# Adafruit-FONA-800-GSM-Breakout.net
KiCad netlist of a schematic drawn in EAGLE
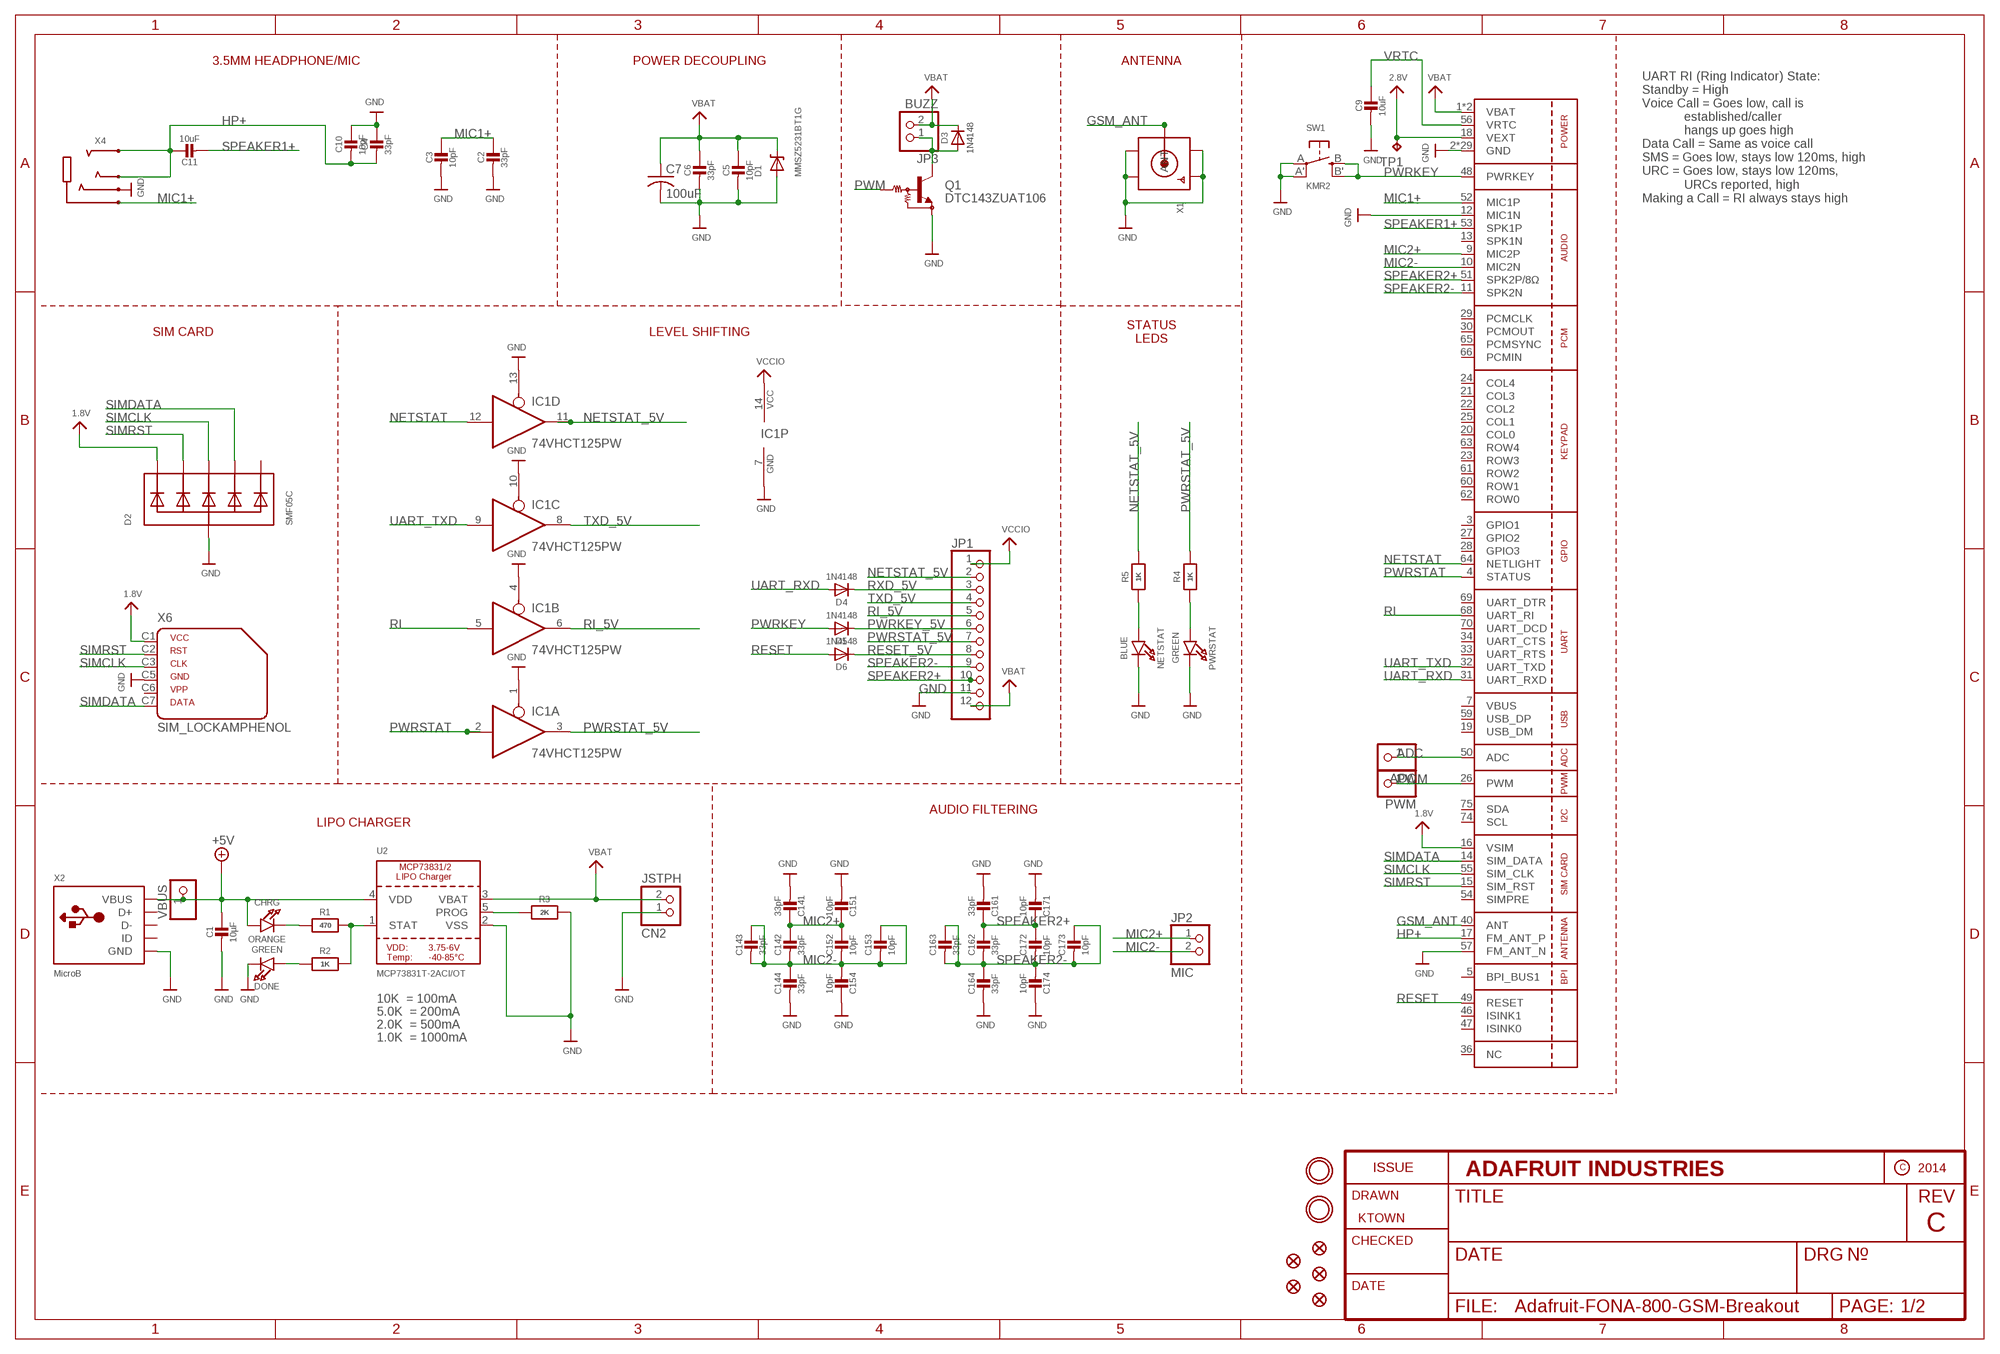
[diagram p0: schematic, sheet 1]
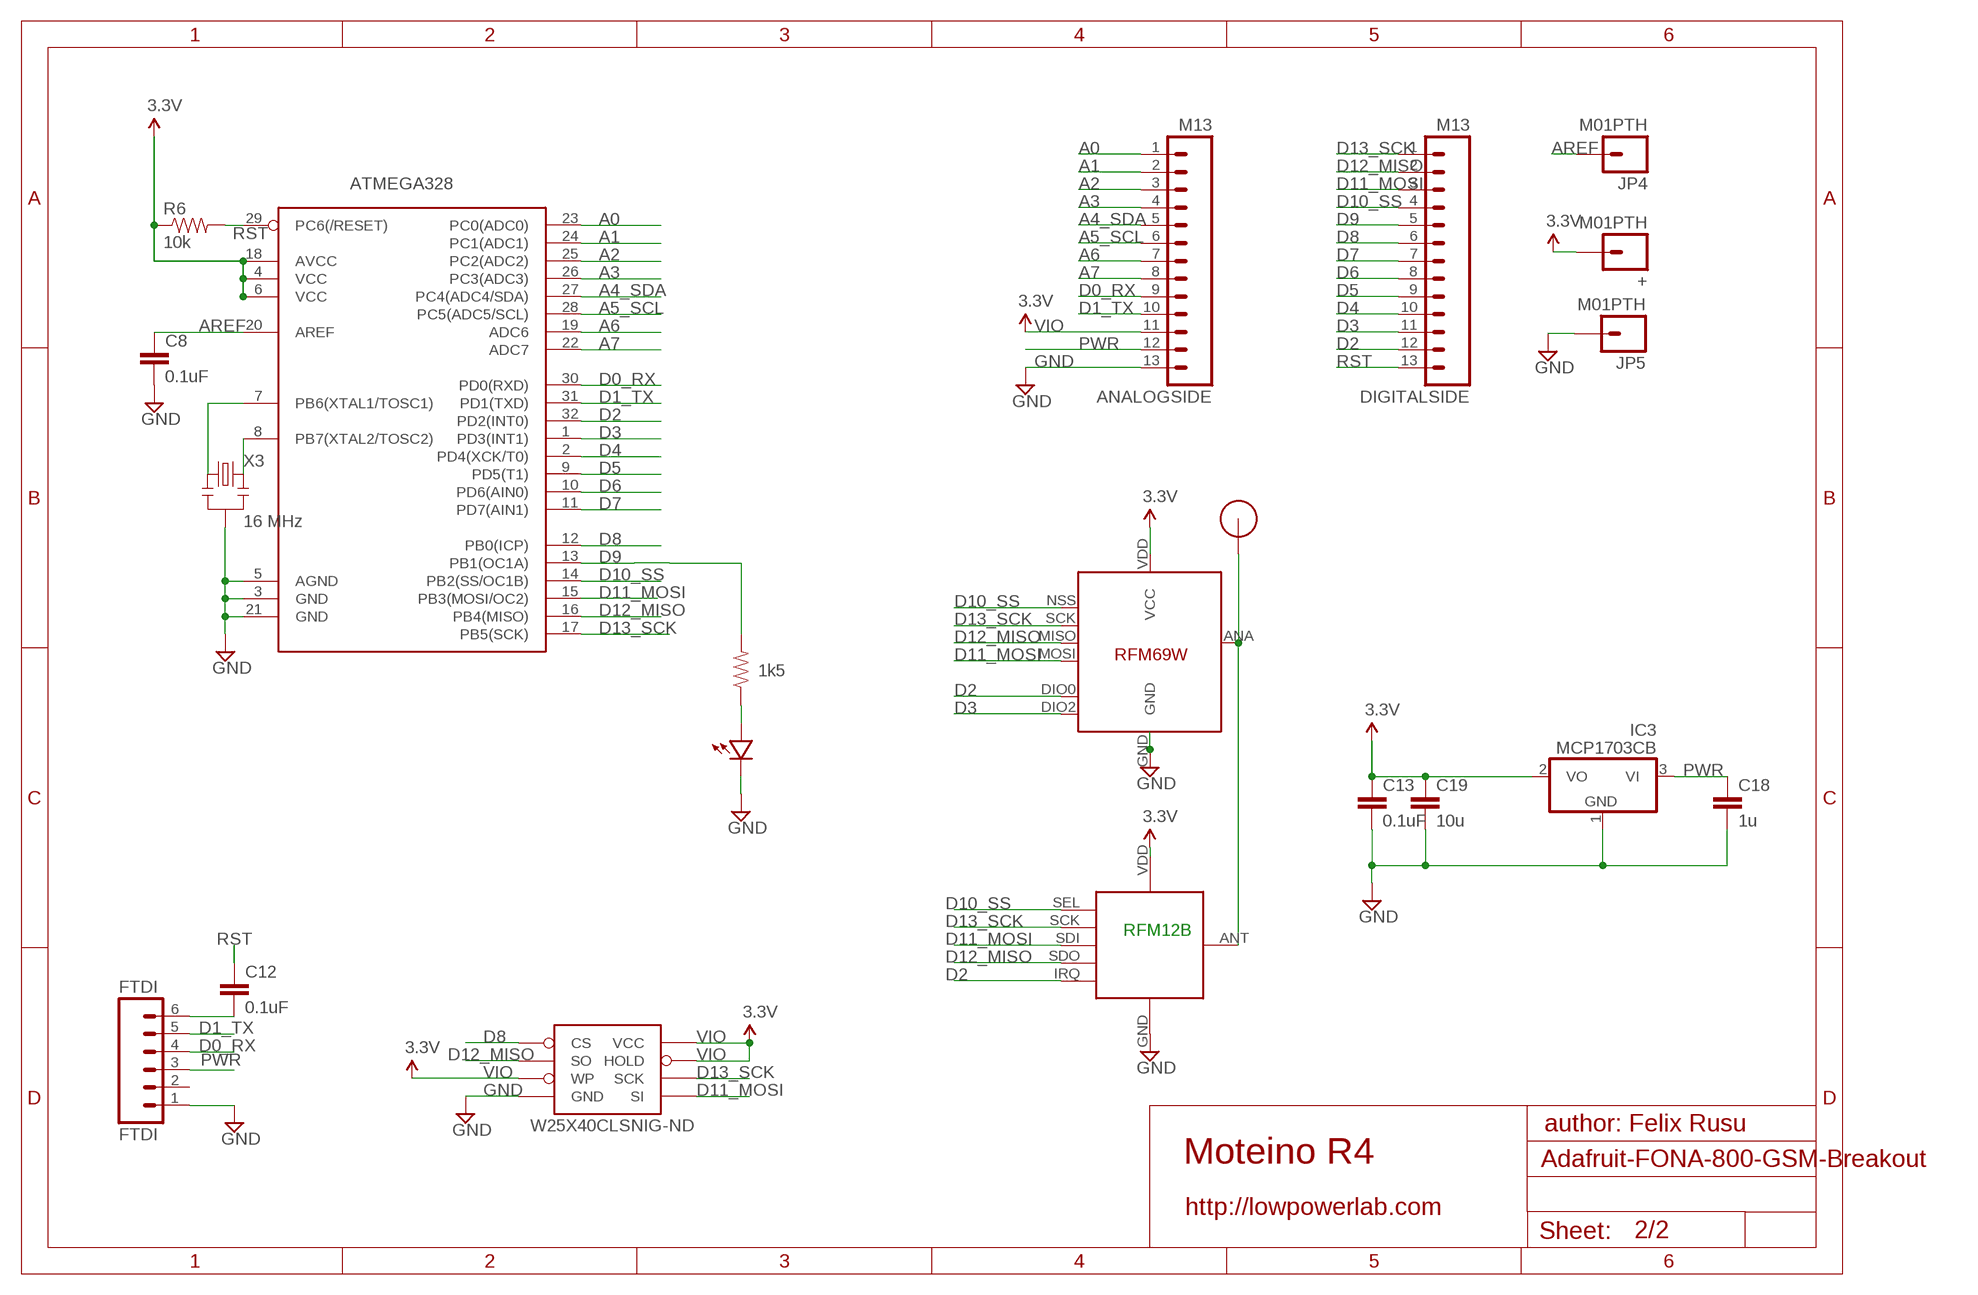
[diagram p1: schematic, sheet 2]

(export (version "E")
  (design (tool "Eeschema 10.0.6"))
  (components
    (comp (ref "ADC")
      (value "PINHD-1X1CB")
      (footprint "eagle-import:1X01-CLEANBIG")
      (libsource (lib "eagle-import") (part "PINHD-1X1CB"))
    )
    (comp (ref "C1")
      (value "10µF")
      (footprint "eagle-import:0805-NO")
      (libsource (lib "eagle-import") (part "CAP_CERAMIC0805-NOOUTLINE"))
    )
    (comp (ref "C2")
      (value "33pF")
      (footprint "eagle-import:0805-NO")
      (libsource (lib "eagle-import") (part "CAP_CERAMIC0805-NOOUTLINE"))
    )
    (comp (ref "C3")
      (value "10pF")
      (footprint "eagle-import:0805-NO")
      (libsource (lib "eagle-import") (part "CAP_CERAMIC0805-NOOUTLINE"))
    )
    (comp (ref "C4")
      (value "33pF")
      (footprint "eagle-import:0805-NO")
      (libsource (lib "eagle-import") (part "CAP_CERAMIC0805-NOOUTLINE"))
    )
    (comp (ref "C5")
      (value "10pF")
      (footprint "eagle-import:0805-NO")
      (libsource (lib "eagle-import") (part "CAP_CERAMIC0805-NOOUTLINE"))
    )
    (comp (ref "C6")
      (value "33pF")
      (footprint "eagle-import:0805-NO")
      (libsource (lib "eagle-import") (part "CAP_CERAMIC0805-NOOUTLINE"))
    )
    (comp (ref "C7")
      (value "100uF")
      (footprint "eagle-import:C1210")
      (libsource (lib "eagle-import") (part "C-USC1210"))
    )
    (comp (ref "C9")
      (value "10uF")
      (footprint "eagle-import:0805-NO")
      (libsource (lib "eagle-import") (part "CAP_CERAMIC0805-NOOUTLINE"))
    )
    (comp (ref "C10")
      (value "10pF")
      (footprint "eagle-import:0805-NO")
      (libsource (lib "eagle-import") (part "CAP_CERAMIC0805-NOOUTLINE"))
    )
    (comp (ref "C11")
      (value "10uF")
      (footprint "eagle-import:0805-NO")
      (libsource (lib "eagle-import") (part "CAP_CERAMIC0805-NOOUTLINE"))
    )
    (comp (ref "C14")
      (value "33pF")
      (footprint "eagle-import:RESPACK_4X0603")
      (libsource (lib "eagle-import") (part "CAP_4PACK1206"))
    )
    (comp (ref "C15")
      (value "10pF")
      (footprint "eagle-import:RESPACK_4X0603")
      (libsource (lib "eagle-import") (part "CAP_4PACK1206"))
    )
    (comp (ref "C16")
      (value "33pF")
      (footprint "eagle-import:RESPACK_4X0603")
      (libsource (lib "eagle-import") (part "CAP_4PACK1206"))
    )
    (comp (ref "C17")
      (value "10pF")
      (footprint "eagle-import:RESPACK_4X0603")
      (libsource (lib "eagle-import") (part "CAP_4PACK1206"))
    )
    (comp (ref "CHRG")
      (value "ORANGE")
      (footprint "eagle-import:CHIPLED_0805_NOOUTLINE")
      (libsource (lib "eagle-import") (part "LED0805_NOOUTLINE"))
    )
    (comp (ref "CN2")
      (value "JSTPH")
      (footprint "eagle-import:JSTPH2")
      (libsource (lib "eagle-import") (part "JST_2PIN"))
    )
    (comp (ref "D1")
      (value "MMSZ5231BT1G")
      (footprint "eagle-import:SOD-123")
      (libsource (lib "eagle-import") (part "DIODE-ZENERSOD123"))
    )
    (comp (ref "D2")
      (value "SMF05C")
      (footprint "eagle-import:SOT363")
      (libsource (lib "eagle-import") (part "TVSARRAY_5LANE"))
    )
    (comp (ref "D3")
      (value "1N4148")
      (footprint "eagle-import:SOD-323")
      (libsource (lib "eagle-import") (part "DIODESOD-323"))
    )
    (comp (ref "D4")
      (value "1N4148")
      (footprint "eagle-import:SOD-323")
      (libsource (lib "eagle-import") (part "DIODESOD-323"))
    )
    (comp (ref "D5")
      (value "1N4148")
      (footprint "eagle-import:SOD-323")
      (libsource (lib "eagle-import") (part "DIODESOD-323"))
    )
    (comp (ref "D6")
      (value "1N4148")
      (footprint "eagle-import:SOD-323")
      (libsource (lib "eagle-import") (part "DIODESOD-323"))
    )
    (comp (ref "DONE")
      (value "GREEN")
      (footprint "eagle-import:CHIPLED_0805_NOOUTLINE")
      (libsource (lib "eagle-import") (part "LED0805_NOOUTLINE"))
    )
    (comp (ref "FID1")
      (value "FIDUCIAL\"\"")
      (footprint "eagle-import:FIDUCIAL_1MM")
      (libsource (lib "eagle-import") (part "FIDUCIAL{dblquote}{dblquote}"))
    )
    (comp (ref "FID2")
      (value "FIDUCIAL\"\"")
      (footprint "eagle-import:FIDUCIAL_1MM")
      (libsource (lib "eagle-import") (part "FIDUCIAL{dblquote}{dblquote}"))
    )
    (comp (ref "FID3")
      (value "FIDUCIAL\"\"")
      (footprint "eagle-import:FIDUCIAL_1MM")
      (libsource (lib "eagle-import") (part "FIDUCIAL{dblquote}{dblquote}"))
    )
    (comp (ref "FID4")
      (value "FIDUCIAL\"\"")
      (footprint "eagle-import:FIDUCIAL_1MM")
      (libsource (lib "eagle-import") (part "FIDUCIAL{dblquote}{dblquote}"))
    )
    (comp (ref "FID5")
      (value "FIDUCIAL\"\"")
      (footprint "eagle-import:FIDUCIAL_1MM")
      (libsource (lib "eagle-import") (part "FIDUCIAL{dblquote}{dblquote}"))
    )
    (comp (ref "IC1")
      (value "74VHCT125PW")
      (footprint "eagle-import:TSSOP14")
      (libsource (lib "eagle-import") (part "74125PWABT"))
    )
    (comp (ref "JP1")
      (value "PINHD-1X12-CB")
      (footprint "eagle-import:1X12-CB")
      (libsource (lib "eagle-import") (part "PINHD-1X12-CB"))
    )
    (comp (ref "JP2")
      (value "MIC")
      (footprint "eagle-import:1X02_ROUND")
      (libsource (lib "eagle-import") (part "HEADER-1X2ROUND"))
    )
    (comp (ref "JP3")
      (value "BUZZ")
      (footprint "eagle-import:1X02_ROUND")
      (libsource (lib "eagle-import") (part "HEADER-1X2ROUND"))
    )
    (comp (ref "NETSTAT")
      (value "BLUE")
      (footprint "eagle-import:CHIPLED_0805_NOOUTLINE")
      (libsource (lib "eagle-import") (part "LED0805_NOOUTLINE"))
    )
    (comp (ref "PWM")
      (value "PINHD-1X1CB")
      (footprint "eagle-import:1X01-CLEANBIG")
      (libsource (lib "eagle-import") (part "PINHD-1X1CB"))
    )
    (comp (ref "PWRSTAT")
      (value "GREEN")
      (footprint "eagle-import:CHIPLED_0805_NOOUTLINE")
      (libsource (lib "eagle-import") (part "LED0805_NOOUTLINE"))
    )
    (comp (ref "Q1")
      (value "DTC143ZUAT106")
      (footprint "eagle-import:SC59-BEC")
      (libsource (lib "eagle-import") (part "-NPN_DRIVER-SC59-BECMUN2211T1"))
    )
    (comp (ref "R1")
      (value "470")
      (footprint "eagle-import:0805-NO")
      (libsource (lib "eagle-import") (part "RESISTOR0805_NOOUTLINE"))
    )
    (comp (ref "R2")
      (value "1K")
      (footprint "eagle-import:0805-NO")
      (libsource (lib "eagle-import") (part "RESISTOR0805_NOOUTLINE"))
    )
    (comp (ref "R3")
      (value "2K")
      (footprint "eagle-import:0805-NO")
      (libsource (lib "eagle-import") (part "RESISTOR0805_NOOUTLINE"))
    )
    (comp (ref "R4")
      (value "1K")
      (footprint "eagle-import:0805-NO")
      (libsource (lib "eagle-import") (part "RESISTOR0805_NOOUTLINE"))
    )
    (comp (ref "R5")
      (value "1K")
      (footprint "eagle-import:0805-NO")
      (libsource (lib "eagle-import") (part "RESISTOR0805_NOOUTLINE"))
    )
    (comp (ref "SW1")
      (value "KMR2")
      (footprint "eagle-import:BTN_KMR2_4.6X2.8")
      (libsource (lib "eagle-import") (part "SWITCH_TACT_SMT4.6X2.8"))
    )
    (comp (ref "TP1")
      (value "TPTP11R")
      (footprint "eagle-import:TP11R")
      (libsource (lib "eagle-import") (part "TPTP11R"))
    )
    (comp (ref "U$33")
      (value "MOUNTINGHOLE2.5")
      (footprint "eagle-import:MOUNTINGHOLE_2.5_PLATED")
      (libsource (lib "eagle-import") (part "MOUNTINGHOLE2.5"))
    )
    (comp (ref "U$34")
      (value "MOUNTINGHOLE2.5")
      (footprint "eagle-import:MOUNTINGHOLE_2.5_PLATED")
      (libsource (lib "eagle-import") (part "MOUNTINGHOLE2.5"))
    )
    (comp (ref "U1")
      (value "SIM800H/L")
      (footprint "eagle-import:SIM800L")
      (libsource (lib "eagle-import") (part "GSM_SIM800L"))
    )
    (comp (ref "U2")
      (value "MCP73831T-2ACI/OT")
      (footprint "eagle-import:SOT23-5")
      (libsource (lib "eagle-import") (part "MCP73831/2"))
    )
    (comp (ref "VBUS")
      (value "PINHD-1X1CB")
      (footprint "eagle-import:1X01-CLEANBIG")
      (libsource (lib "eagle-import") (part "PINHD-1X1CB"))
    )
    (comp (ref "X1")
      (value "SMACONNECTOR_EDGE_UFL")
      (footprint "eagle-import:SMA_EDGELAUNCH_UFL")
      (libsource (lib "eagle-import") (part "SMACONNECTOR_EDGE_UFL"))
    )
    (comp (ref "X2")
      (value "MicroB")
      (footprint "eagle-import:4UCONN_20329")
      (libsource (lib "eagle-import") (part "USBMICRO_20329"))
    )
    (comp (ref "X4")
      (value "AUDIO_3.5MMJACK_4POL")
      (footprint "eagle-import:4UCONN_18510")
      (libsource (lib "eagle-import") (part "AUDIO_3.5MMJACK_4POL"))
    )
    (comp (ref "X6")
      (value "SIM_LOCKAMPHENOL")
      (footprint "eagle-import:C707_10M006_512_2")
      (libsource (lib "eagle-import") (part "SIM_LOCKAMPHENOL"))
    )
    (comp (ref "+")
      (value "M01PTH")
      (footprint "eagle-import:1X01")
      (libsource (lib "eagle-import") (part "M01PTH"))
    )
    (comp (ref "ANALOGSIDE")
      (value "M13")
      (footprint "eagle-import:1X13")
      (libsource (lib "eagle-import") (part "M13"))
    )
    (comp (ref "ATMEGA328")
      (value "ATMega-328")
      (footprint "eagle-import:TQFP32-08")
      (libsource (lib "eagle-import") (part "ATMEGA168/328TQFP32"))
    )
    (comp (ref "C8")
      (value "0.1uF")
      (footprint "eagle-import:0603-CAP")
      (libsource (lib "eagle-import") (part "CAP0603-CAP"))
    )
    (comp (ref "C12")
      (value "0.1uF")
      (footprint "eagle-import:0603-CAP")
      (libsource (lib "eagle-import") (part "CAP0603-CAP"))
    )
    (comp (ref "C13")
      (value "0.1uF")
      (footprint "eagle-import:0603-CAP")
      (libsource (lib "eagle-import") (part "CAP0603-CAP"))
    )
    (comp (ref "C18")
      (value "1u")
      (footprint "eagle-import:0603-CAP")
      (libsource (lib "eagle-import") (part "CAP0603-CAP"))
    )
    (comp (ref "C19")
      (value "10u")
      (footprint "eagle-import:0805-CAP")
      (libsource (lib "eagle-import") (part "CAP0805-CAP"))
    )
    (comp (ref "DIGITALSIDE")
      (value "M13")
      (footprint "eagle-import:1X13")
      (libsource (lib "eagle-import") (part "M13"))
    )
    (comp (ref "FTDI")
      (value "FTDI")
      (footprint "eagle-import:1X06")
      (libsource (lib "eagle-import") (part "M06SIP"))
    )
    (comp (ref "IC3")
      (value "MCP1703CB")
      (footprint "eagle-import:SOT23")
      (libsource (lib "eagle-import") (part "MCP1703CB"))
    )
    (comp (ref "JP4")
      (value "M01PTH")
      (footprint "eagle-import:1X01")
      (libsource (lib "eagle-import") (part "M01PTH"))
    )
    (comp (ref "JP5")
      (value "M01PTH")
      (footprint "eagle-import:1X01")
      (libsource (lib "eagle-import") (part "M01PTH"))
    )
    (comp (ref "R6")
      (value "10k")
      (footprint "eagle-import:0603-RES")
      (libsource (lib "eagle-import") (part "RESISTOR0603-RES"))
    )
    (comp (ref "R7")
      (value "1k5")
      (footprint "eagle-import:0603-RES")
      (libsource (lib "eagle-import") (part "RESISTOR0603-RES"))
    )
    (comp (ref "RFM12B")
      (value "RFM12B_MINPADS")
      (footprint "eagle-import:RFM12B-MINPADS")
      (libsource (lib "eagle-import") (part "RFM12B_MINPADS"))
    )
    (comp (ref "U$38")
      (value "LED0603")
      (footprint "eagle-import:0603-LED")
      (libsource (lib "eagle-import") (part "LED0603"))
    )
    (comp (ref "U$39")
      (value "RFM12B_ANTENNA")
      (footprint "eagle-import:RFM12B-ANTENNA")
      (libsource (lib "eagle-import") (part "RFM12B_ANTENNA"))
    )
    (comp (ref "U$42")
      (value "RFM69")
      (footprint "eagle-import:RFM69W-MINPADS")
      (libsource (lib "eagle-import") (part "RFM69"))
    )
    (comp (ref "W25X40CLSNIG-ND")
      (value "AT25F512BWIDE_5.3MM")
      (footprint "eagle-import:SO08WIDE")
      (libsource (lib "eagle-import") (part "AT25F512BWIDE_5.3MM"))
    )
    (comp (ref "X3")
      (value "16 MHz")
      (footprint "eagle-import:RESONATOR-SMD")
      (libsource (lib "eagle-import") (part "RESONATORSMD"))
    )
  )
  (nets
    (net (code "1") (name "+5V") (class "Default")
      (node (ref "C1") (pin "1") (pinfunction "1_1") (pintype "passive"))
      (node (ref "CHRG") (pin "A") (pinfunction "A_A") (pintype "passive"))
      (node (ref "U2") (pin "4") (pinfunction "VDD_4") (pintype "power_in"))
      (node (ref "VBUS") (pin "1") (pinfunction "1_1") (pintype "passive"))
      (node (ref "X2") (pin "VBUS") (pinfunction "VBUS_VBUS") (pintype "power_in"))
    )
    (net (code "2") (name "1.8V") (class "Default")
      (node (ref "D2") (pin "1") (pinfunction "C1_1") (pintype "passive"))
      (node (ref "U1") (pin "16") (pinfunction "VSIM_16") (pintype "power_in"))
      (node (ref "X6") (pin "C1") (pinfunction "1_C1") (pintype "passive"))
    )
    (net (code "3") (name "2.8V") (class "Default")
      (node (ref "TP1") (pin "TP") (pinfunction "TP_TP") (pintype "input"))
      (node (ref "U1") (pin "18") (pinfunction "VEXT_18") (pintype "power_in"))
    )
    (net (code "4") (name "A0") (class "Default")
      (node (ref "ANALOGSIDE") (pin "1") (pinfunction "1_1") (pintype "passive"))
      (node (ref "ATMEGA328") (pin "23") (pinfunction "PC0(ADC0)_23") (pintype "bidirectional"))
    )
    (net (code "5") (name "A1") (class "Default")
      (node (ref "ANALOGSIDE") (pin "2") (pinfunction "2_2") (pintype "passive"))
      (node (ref "ATMEGA328") (pin "24") (pinfunction "PC1(ADC1)_24") (pintype "bidirectional"))
    )
    (net (code "6") (name "A2") (class "Default")
      (node (ref "ANALOGSIDE") (pin "3") (pinfunction "3_3") (pintype "passive"))
      (node (ref "ATMEGA328") (pin "25") (pinfunction "PC2(ADC2)_25") (pintype "bidirectional"))
    )
    (net (code "7") (name "A3") (class "Default")
      (node (ref "ANALOGSIDE") (pin "4") (pinfunction "4_4") (pintype "passive"))
      (node (ref "ATMEGA328") (pin "26") (pinfunction "PC3(ADC3)_26") (pintype "bidirectional"))
    )
    (net (code "8") (name "A4_SDA") (class "Default")
      (node (ref "ANALOGSIDE") (pin "5") (pinfunction "5_5") (pintype "passive"))
      (node (ref "ATMEGA328") (pin "27") (pinfunction "PC4(ADC4/SDA)_27") (pintype "bidirectional"))
    )
    (net (code "9") (name "A5_SCL") (class "Default")
      (node (ref "ANALOGSIDE") (pin "6") (pinfunction "6_6") (pintype "passive"))
      (node (ref "ATMEGA328") (pin "28") (pinfunction "PC5(ADC5/SCL)_28") (pintype "bidirectional"))
    )
    (net (code "10") (name "A6") (class "Default")
      (node (ref "ANALOGSIDE") (pin "7") (pinfunction "7_7") (pintype "passive"))
      (node (ref "ATMEGA328") (pin "19") (pinfunction "ADC6_19") (pintype "bidirectional"))
    )
    (net (code "11") (name "A7") (class "Default")
      (node (ref "ANALOGSIDE") (pin "8") (pinfunction "8_8") (pintype "passive"))
      (node (ref "ATMEGA328") (pin "22") (pinfunction "ADC7_22") (pintype "bidirectional"))
    )
    (net (code "12") (name "ADC") (class "Default")
      (node (ref "ADC") (pin "1") (pinfunction "1_1") (pintype "passive"))
      (node (ref "U1") (pin "50") (pinfunction "ADC_50") (pintype "input"))
    )
    (net (code "13") (name "AREF") (class "Default")
      (node (ref "ATMEGA328") (pin "20") (pinfunction "AREF_20") (pintype "bidirectional"))
      (node (ref "C8") (pin "1") (pinfunction "1_1") (pintype "passive"))
      (node (ref "JP4") (pin "1") (pinfunction "1_1") (pintype "passive"))
    )
    (net (code "14") (name "D0_RX") (class "Default")
      (node (ref "ANALOGSIDE") (pin "9") (pinfunction "9_9") (pintype "passive"))
      (node (ref "ATMEGA328") (pin "30") (pinfunction "PD0(RXD)_30") (pintype "bidirectional"))
      (node (ref "FTDI") (pin "4") (pinfunction "4_4") (pintype "passive"))
    )
    (net (code "15") (name "D1_TX") (class "Default")
      (node (ref "ANALOGSIDE") (pin "10") (pinfunction "10_10") (pintype "passive"))
      (node (ref "ATMEGA328") (pin "31") (pinfunction "PD1(TXD)_31") (pintype "bidirectional"))
      (node (ref "FTDI") (pin "5") (pinfunction "5_5") (pintype "passive"))
    )
    (net (code "16") (name "D2") (class "Default")
      (node (ref "ATMEGA328") (pin "32") (pinfunction "PD2(INT0)_32") (pintype "bidirectional"))
      (node (ref "DIGITALSIDE") (pin "12") (pinfunction "12_12") (pintype "passive"))
      (node (ref "RFM12B") (pin "IRQ") (pinfunction "IRQ_IRQ") (pintype "bidirectional"))
      (node (ref "U$42") (pin "DIO0") (pinfunction "DIO0_DIO0") (pintype "open_collector"))
    )
    (net (code "17") (name "D3") (class "Default")
      (node (ref "ATMEGA328") (pin "1") (pinfunction "PD3(INT1)_1") (pintype "bidirectional"))
      (node (ref "DIGITALSIDE") (pin "11") (pinfunction "11_11") (pintype "passive"))
      (node (ref "U$42") (pin "DIO2") (pinfunction "DIO2_DIO2") (pintype "open_collector"))
    )
    (net (code "18") (name "D4") (class "Default")
      (node (ref "ATMEGA328") (pin "2") (pinfunction "PD4(XCK/T0)_2") (pintype "bidirectional"))
      (node (ref "DIGITALSIDE") (pin "10") (pinfunction "10_10") (pintype "passive"))
    )
    (net (code "19") (name "D5") (class "Default")
      (node (ref "ATMEGA328") (pin "9") (pinfunction "PD5(T1)_9") (pintype "bidirectional"))
      (node (ref "DIGITALSIDE") (pin "9") (pinfunction "9_9") (pintype "passive"))
    )
    (net (code "20") (name "D6") (class "Default")
      (node (ref "ATMEGA328") (pin "10") (pinfunction "PD6(AIN0)_10") (pintype "bidirectional"))
      (node (ref "DIGITALSIDE") (pin "8") (pinfunction "8_8") (pintype "passive"))
    )
    (net (code "21") (name "D7") (class "Default")
      (node (ref "ATMEGA328") (pin "11") (pinfunction "PD7(AIN1)_11") (pintype "bidirectional"))
      (node (ref "DIGITALSIDE") (pin "7") (pinfunction "7_7") (pintype "passive"))
    )
    (net (code "22") (name "D8") (class "Default")
      (node (ref "ATMEGA328") (pin "12") (pinfunction "PB0(ICP)_12") (pintype "bidirectional"))
      (node (ref "DIGITALSIDE") (pin "6") (pinfunction "6_6") (pintype "passive"))
      (node (ref "W25X40CLSNIG-ND") (pin "1") (pinfunction "CS_1") (pintype "bidirectional"))
    )
    (net (code "23") (name "D9") (class "Default")
      (node (ref "ATMEGA328") (pin "13") (pinfunction "PB1(OC1A)_13") (pintype "bidirectional"))
      (node (ref "DIGITALSIDE") (pin "5") (pinfunction "5_5") (pintype "passive"))
      (node (ref "R7") (pin "2") (pinfunction "2_2") (pintype "passive"))
    )
    (net (code "24") (name "D10_SS") (class "Default")
      (node (ref "ATMEGA328") (pin "14") (pinfunction "PB2(SS/OC1B)_14") (pintype "bidirectional"))
      (node (ref "DIGITALSIDE") (pin "4") (pinfunction "4_4") (pintype "passive"))
      (node (ref "RFM12B") (pin "SEL") (pinfunction "SEL_SEL") (pintype "bidirectional"))
      (node (ref "U$42") (pin "NSS") (pinfunction "SEL_NSS") (pintype "input"))
    )
    (net (code "25") (name "D11_MOSI") (class "Default")
      (node (ref "ATMEGA328") (pin "15") (pinfunction "PB3(MOSI/OC2)_15") (pintype "bidirectional"))
      (node (ref "DIGITALSIDE") (pin "3") (pinfunction "3_3") (pintype "passive"))
      (node (ref "RFM12B") (pin "SDI") (pinfunction "SDI/MOSI_SDI") (pintype "bidirectional"))
      (node (ref "U$42") (pin "MOSI") (pinfunction "MOSI_MOSI") (pintype "output"))
      (node (ref "W25X40CLSNIG-ND") (pin "5") (pinfunction "SI_5") (pintype "bidirectional"))
    )
    (net (code "26") (name "D12_MISO") (class "Default")
      (node (ref "ATMEGA328") (pin "16") (pinfunction "PB4(MISO)_16") (pintype "bidirectional"))
      (node (ref "DIGITALSIDE") (pin "2") (pinfunction "2_2") (pintype "passive"))
      (node (ref "RFM12B") (pin "SDO") (pinfunction "SDO/MISO_SDO") (pintype "bidirectional"))
      (node (ref "U$42") (pin "MISO") (pinfunction "MISO_MISO") (pintype "input"))
      (node (ref "W25X40CLSNIG-ND") (pin "2") (pinfunction "SO_2") (pintype "bidirectional"))
    )
    (net (code "27") (name "D13_SCK") (class "Default")
      (node (ref "ATMEGA328") (pin "17") (pinfunction "PB5(SCK)_17") (pintype "bidirectional"))
      (node (ref "DIGITALSIDE") (pin "1") (pinfunction "1_1") (pintype "passive"))
      (node (ref "RFM12B") (pin "SCK") (pinfunction "SCK_SCK") (pintype "bidirectional"))
      (node (ref "U$42") (pin "SCK") (pinfunction "SCK_SCK") (pintype "input"))
      (node (ref "W25X40CLSNIG-ND") (pin "6") (pinfunction "SCK_6") (pintype "bidirectional"))
    )
    (net (code "28") (name "GND") (class "Default")
      (node (ref "ANALOGSIDE") (pin "13") (pinfunction "13_13") (pintype "passive"))
      (node (ref "ATMEGA328") (pin "21") (pinfunction "GND_21") (pintype "bidirectional"))
      (node (ref "ATMEGA328") (pin "3") (pinfunction "GND_3") (pintype "bidirectional"))
      (node (ref "ATMEGA328") (pin "5") (pinfunction "AGND_5") (pintype "bidirectional"))
      (node (ref "C1") (pin "2") (pinfunction "2_2") (pintype "passive"))
      (node (ref "C10") (pin "1") (pinfunction "1_1") (pintype "passive"))
      (node (ref "C13") (pin "2") (pinfunction "2_2") (pintype "passive"))
      (node (ref "C14") (pin "5") (pinfunction "2_5") (pintype "passive"))
      (node (ref "C14") (pin "8") (pinfunction "2_8") (pintype "passive"))
      (node (ref "C15") (pin "4") (pinfunction "1_4") (pintype "passive"))
      (node (ref "C15") (pin "8") (pinfunction "2_8") (pintype "passive"))
      (node (ref "C16") (pin "5") (pinfunction "2_5") (pintype "passive"))
      (node (ref "C16") (pin "8") (pinfunction "2_8") (pintype "passive"))
      (node (ref "C17") (pin "4") (pinfunction "1_4") (pintype "passive"))
      (node (ref "C17") (pin "8") (pinfunction "2_8") (pintype "passive"))
      (node (ref "C18") (pin "2") (pinfunction "2_2") (pintype "passive"))
      (node (ref "C19") (pin "2") (pinfunction "2_2") (pintype "passive"))
      (node (ref "C2") (pin "2") (pinfunction "2_2") (pintype "passive"))
      (node (ref "C3") (pin "2") (pinfunction "2_2") (pintype "passive"))
      (node (ref "C4") (pin "1") (pinfunction "1_1") (pintype "passive"))
      (node (ref "C5") (pin "2") (pinfunction "2_2") (pintype "passive"))
      (node (ref "C6") (pin "2") (pinfunction "2_2") (pintype "passive"))
      (node (ref "C7") (pin "2") (pinfunction "2_2") (pintype "passive"))
      (node (ref "C8") (pin "2") (pinfunction "2_2") (pintype "passive"))
      (node (ref "C9") (pin "2") (pinfunction "2_2") (pintype "passive"))
      (node (ref "CN2") (pin "1") (pinfunction "1_1") (pintype "passive"))
      (node (ref "D1") (pin "A") (pinfunction "A_A") (pintype "passive"))
      (node (ref "D2") (pin "2") (pinfunction "A_2") (pintype "passive"))
      (node (ref "DONE") (pin "C") (pinfunction "C_C") (pintype "passive"))
      (node (ref "FTDI") (pin "1") (pinfunction "1_1") (pintype "passive"))
      (node (ref "IC1") (pin "1") (pinfunction "OE_1") (pintype "input"))
      (node (ref "IC1") (pin "10") (pinfunction "OE_10") (pintype "input"))
      (node (ref "IC1") (pin "13") (pinfunction "OE_13") (pintype "input"))
      (node (ref "IC1") (pin "4") (pinfunction "OE_4") (pintype "input"))
      (node (ref "IC1") (pin "7") (pinfunction "GND_7") (pintype "power_in"))
      (node (ref "IC3") (pin "1") (pinfunction "GND_1") (pintype "passive"))
      (node (ref "JP1") (pin "11") (pinfunction "11_11") (pintype "passive"))
      (node (ref "JP5") (pin "1") (pinfunction "1_1") (pintype "passive"))
      (node (ref "NETSTAT") (pin "C") (pinfunction "C_C") (pintype "passive"))
      (node (ref "PWRSTAT") (pin "C") (pinfunction "C_C") (pintype "passive"))
      (node (ref "Q1") (pin "E") (pinfunction "E_E") (pintype "passive"))
      (node (ref "R3") (pin "2") (pinfunction "2_2") (pintype "passive"))
      (node (ref "RFM12B") (pin "GND") (pinfunction "GND_GND") (pintype "bidirectional"))
      (node (ref "SW1") (pin "A") (pinfunction "P_A") (pintype "passive"))
      (node (ref "SW1") (pin "A'") (pinfunction "P1_A'") (pintype "passive"))
      (node (ref "U$38") (pin "MINUS") (pinfunction "MINUS_MINUS") (pintype "passive"))
      (node (ref "U$42") (pin "GND") (pinfunction "GND_GND") (pintype "power_in"))
      (node (ref "U1") (pin "12") (pinfunction "MIC1N_12") (pintype "input"))
      (node (ref "U1") (pin "2") (pinfunction "GND_2") (pintype "power_in"))
      (node (ref "U1") (pin "35") (pinfunction "GND_35") (pintype "power_in"))
      (node (ref "U1") (pin "37") (pinfunction "GND_37") (pintype "power_in"))
      (node (ref "U1") (pin "38") (pinfunction "GND_38") (pintype "power_in"))
      (node (ref "U1") (pin "39") (pinfunction "GND_39") (pintype "power_in"))
      (node (ref "U1") (pin "41") (pinfunction "GND_41") (pintype "power_in"))
      (node (ref "U1") (pin "43") (pinfunction "GND_43") (pintype "power_in"))
      (node (ref "U1") (pin "44") (pinfunction "GND_44") (pintype "power_in"))
      (node (ref "U1") (pin "45") (pinfunction "GND_45") (pintype "power_in"))
      (node (ref "U1") (pin "57") (pinfunction "FM_ANT_N_57") (pintype "bidirectional"))
      (node (ref "U1") (pin "58") (pinfunction "GND_58") (pintype "power_in"))
      (node (ref "U1") (pin "6") (pinfunction "GND_6") (pintype "power_in"))
      (node (ref "U1") (pin "67") (pinfunction "GND_67") (pintype "power_in"))
      (node (ref "U1") (pin "71") (pinfunction "GND_71") (pintype "power_in"))
      (node (ref "U1") (pin "72") (pinfunction "GND_72") (pintype "power_in"))
      (node (ref "U1") (pin "73") (pinfunction "GND_73") (pintype "power_in"))
      (node (ref "U1") (pin "76") (pinfunction "GND_76") (pintype "power_in"))
      (node (ref "U1") (pin "77") (pinfunction "GND_77") (pintype "power_in"))
      (node (ref "U1") (pin "78") (pinfunction "GND_78") (pintype "power_in"))
      (node (ref "U1") (pin "79") (pinfunction "GND_79") (pintype "power_in"))
      (node (ref "U1") (pin "8") (pinfunction "GND_8") (pintype "power_in"))
      (node (ref "U1") (pin "80") (pinfunction "GND_80") (pintype "power_in"))
      (node (ref "U1") (pin "81") (pinfunction "GND_81") (pintype "power_in"))
      (node (ref "U1") (pin "82") (pinfunction "GND_82") (pintype "power_in"))
      (node (ref "U1") (pin "83") (pinfunction "GND_83") (pintype "power_in"))
      (node (ref "U1") (pin "84") (pinfunction "GND_84") (pintype "power_in"))
      (node (ref "U1") (pin "85") (pinfunction "GND_85") (pintype "power_in"))
      (node (ref "U1") (pin "86") (pinfunction "GND_86") (pintype "power_in"))
      (node (ref "U1") (pin "87") (pinfunction "GND_87") (pintype "power_in"))
      (node (ref "U1") (pin "88") (pinfunction "GND_88") (pintype "power_in"))
      (node (ref "U2") (pin "2") (pinfunction "VSS_2") (pintype "power_in"))
      (node (ref "W25X40CLSNIG-ND") (pin "4") (pinfunction "GND_4") (pintype "bidirectional"))
      (node (ref "X1") (pin "GND@1") (pinfunction "GND1_GND@1") (pintype "power_in"))
      (node (ref "X1") (pin "GND@2") (pinfunction "GND2_GND@2") (pintype "power_in"))
      (node (ref "X1") (pin "GND@3") (pinfunction "GND3_GND@3") (pintype "power_in"))
      (node (ref "X1") (pin "GND@4") (pinfunction "GND4_GND@4") (pintype "power_in"))
      (node (ref "X2") (pin "BASE@1") (pinfunction "GND_BASE@1") (pintype "power_in"))
      (node (ref "X2") (pin "BASE@2") (pinfunction "GND_BASE@2") (pintype "power_in"))
      (node (ref "X2") (pin "GND") (pinfunction "GND_GND") (pintype "power_in"))
      (node (ref "X2") (pin "SPRT@1") (pinfunction "GND_SPRT@1") (pintype "power_in"))
      (node (ref "X2") (pin "SPRT@2") (pinfunction "GND_SPRT@2") (pintype "power_in"))
      (node (ref "X2") (pin "SPRT@3") (pinfunction "GND_SPRT@3") (pintype "power_in"))
      (node (ref "X2") (pin "SPRT@4") (pinfunction "GND_SPRT@4") (pintype "power_in"))
      (node (ref "X3") (pin "2") (pinfunction "2_2") (pintype "passive"))
      (node (ref "X4") (pin "4-INNER_SLEEVE") (pinfunction "RING1_4-INNER_SLEEVE") (pintype "passive"))
      (node (ref "X6") (pin "C5") (pinfunction "4_C5") (pintype "passive"))
    )
    (net (code "29") (name "GSM_ANT") (class "Default")
      (node (ref "U1") (pin "40") (pinfunction "ANT_40") (pintype "bidirectional"))
      (node (ref "X1") (pin "P") (pinfunction "ANT_P") (pintype "bidirectional"))
    )
    (net (code "30") (name "HP+") (class "Default")
      (node (ref "C10") (pin "2") (pinfunction "2_2") (pintype "passive"))
      (node (ref "C11") (pin "1") (pinfunction "1_1") (pintype "passive"))
      (node (ref "C4") (pin "2") (pinfunction "2_2") (pintype "passive"))
      (node (ref "U1") (pin "17") (pinfunction "FM_ANT_P_17") (pintype "bidirectional"))
      (node (ref "X4") (pin "2-TIP") (pinfunction "RING3_2-TIP") (pintype "passive"))
      (node (ref "X4") (pin "3-OUTER_SLEEVE") (pinfunction "RING2_3-OUTER_SLEEVE") (pintype "passive"))
    )
    (net (code "31") (name "MIC1+") (class "Default")
      (node (ref "C2") (pin "1") (pinfunction "1_1") (pintype "passive"))
      (node (ref "C3") (pin "1") (pinfunction "1_1") (pintype "passive"))
      (node (ref "U1") (pin "52") (pinfunction "MIC1P_52") (pintype "input"))
      (node (ref "X4") (pin "1-GND") (pinfunction "TIP_1-GND") (pintype "passive"))
    )
    (net (code "32") (name "MIC2+") (class "Default")
      (node (ref "C14") (pin "1") (pinfunction "1_1") (pintype "passive"))
      (node (ref "C14") (pin "2") (pinfunction "1_2") (pintype "passive"))
      (node (ref "C15") (pin "1") (pinfunction "1_1") (pintype "passive"))
      (node (ref "C15") (pin "2") (pinfunction "1_2") (pintype "passive"))
      (node (ref "JP2") (pin "1") (pinfunction "1_1") (pintype "passive"))
      (node (ref "U1") (pin "9") (pinfunction "MIC2P_9") (pintype "input"))
    )
    (net (code "33") (name "MIC2-") (class "Default")
      (node (ref "C14") (pin "3") (pinfunction "1_3") (pintype "passive"))
      (node (ref "C14") (pin "4") (pinfunction "1_4") (pintype "passive"))
      (node (ref "C14") (pin "6") (pinfunction "2_6") (pintype "passive"))
      (node (ref "C14") (pin "7") (pinfunction "2_7") (pintype "passive"))
      (node (ref "C15") (pin "3") (pinfunction "1_3") (pintype "passive"))
      (node (ref "C15") (pin "5") (pinfunction "2_5") (pintype "passive"))
      (node (ref "C15") (pin "6") (pinfunction "2_6") (pintype "passive"))
      (node (ref "C15") (pin "7") (pinfunction "2_7") (pintype "passive"))
      (node (ref "JP2") (pin "2") (pinfunction "2_2") (pintype "passive"))
      (node (ref "U1") (pin "10") (pinfunction "MIC2N_10") (pintype "input"))
    )
    (net (code "34") (name "NETSTAT") (class "Default")
      (node (ref "IC1") (pin "12") (pinfunction "I_12") (pintype "input"))
      (node (ref "U1") (pin "64") (pinfunction "NETLIGHT_64") (pintype "output"))
    )
    (net (code "35") (name "NETSTAT_5V") (class "Default")
      (node (ref "IC1") (pin "11") (pinfunction "O_11") (pintype "tri_state"))
      (node (ref "JP1") (pin "2") (pinfunction "2_2") (pintype "passive"))
      (node (ref "R5") (pin "2") (pinfunction "2_2") (pintype "passive"))
    )
    (net (code "36") (name "Net-(ATMEGA328-PB6(XTAL1{slash}TOSC1))") (class "Default")
      (node (ref "ATMEGA328") (pin "7") (pinfunction "PB6(XTAL1/TOSC1)_7") (pintype "bidirectional"))
      (node (ref "X3") (pin "1") (pinfunction "1_1") (pintype "passive"))
    )
    (net (code "37") (name "Net-(ATMEGA328-PB7(XTAL2{slash}TOSC2))") (class "Default")
      (node (ref "ATMEGA328") (pin "8") (pinfunction "PB7(XTAL2/TOSC2)_8") (pintype "bidirectional"))
      (node (ref "X3") (pin "3") (pinfunction "3_3") (pintype "passive"))
    )
    (net (code "38") (name "Net-(C12-Pad2)") (class "Default")
      (node (ref "C12") (pin "2") (pinfunction "2_2") (pintype "passive"))
      (node (ref "FTDI") (pin "6") (pinfunction "6_6") (pintype "passive"))
    )
    (net (code "39") (name "Net-(CHRG-PadC)") (class "Default")
      (node (ref "CHRG") (pin "C") (pinfunction "C_C") (pintype "passive"))
      (node (ref "R1") (pin "1") (pinfunction "1_1") (pintype "passive"))
    )
    (net (code "40") (name "Net-(D3-PadA)") (class "Default")
      (node (ref "D3") (pin "A") (pinfunction "A_A") (pintype "passive"))
      (node (ref "JP3") (pin "1") (pinfunction "1_1") (pintype "passive"))
      (node (ref "Q1") (pin "C") (pinfunction "C_C") (pintype "passive"))
    )
    (net (code "41") (name "Net-(DONE-PadA)") (class "Default")
      (node (ref "DONE") (pin "A") (pinfunction "A_A") (pintype "passive"))
      (node (ref "R2") (pin "1") (pinfunction "1_1") (pintype "passive"))
    )
    (net (code "42") (name "Net-(NETSTAT-PadA)") (class "Default")
      (node (ref "NETSTAT") (pin "A") (pinfunction "A_A") (pintype "passive"))
      (node (ref "R5") (pin "1") (pinfunction "1_1") (pintype "passive"))
    )
    (net (code "43") (name "Net-(PWRSTAT-PadA)") (class "Default")
      (node (ref "PWRSTAT") (pin "A") (pinfunction "A_A") (pintype "passive"))
      (node (ref "R4") (pin "1") (pinfunction "1_1") (pintype "passive"))
    )
    (net (code "44") (name "Net-(R7-Pad1)") (class "Default")
      (node (ref "R7") (pin "1") (pinfunction "1_1") (pintype "passive"))
      (node (ref "U$38") (pin "PLUS") (pinfunction "PLUS_PLUS") (pintype "passive"))
    )
    (net (code "45") (name "Net-(U$39-1)") (class "Default")
      (node (ref "RFM12B") (pin "ANT") (pinfunction "ANT_ANT") (pintype "bidirectional"))
      (node (ref "U$39") (pin "P$1") (pinfunction "1_P$1") (pintype "bidirectional"))
      (node (ref "U$42") (pin "ANA") (pinfunction "ANT_ANA") (pintype "passive"))
    )
    (net (code "46") (name "Net-(U2-PROG)") (class "Default")
      (node (ref "R3") (pin "1") (pinfunction "1_1") (pintype "passive"))
      (node (ref "U2") (pin "5") (pinfunction "PROG_5") (pintype "input"))
    )
    (net (code "47") (name "Net-(U2-STAT)") (class "Default")
      (node (ref "R1") (pin "2") (pinfunction "2_2") (pintype "passive"))
      (node (ref "R2") (pin "2") (pinfunction "2_2") (pintype "passive"))
      (node (ref "U2") (pin "1") (pinfunction "STAT_1") (pintype "output"))
    )
    (net (code "48") (name "PWM") (class "Default")
      (node (ref "PWM") (pin "1") (pinfunction "1_1") (pintype "passive"))
      (node (ref "Q1") (pin "B") (pinfunction "B_B") (pintype "passive"))
      (node (ref "U1") (pin "26") (pinfunction "PWM_26") (pintype "output"))
    )
    (net (code "49") (name "PWR") (class "Default")
      (node (ref "ANALOGSIDE") (pin "12") (pinfunction "12_12") (pintype "passive"))
      (node (ref "C18") (pin "1") (pinfunction "1_1") (pintype "passive"))
      (node (ref "FTDI") (pin "3") (pinfunction "3_3") (pintype "passive"))
      (node (ref "IC3") (pin "3") (pinfunction "VI_3") (pintype "input"))
    )
    (net (code "50") (name "PWRKEY") (class "Default")
      (node (ref "D5") (pin "A") (pinfunction "A_A") (pintype "passive"))
      (node (ref "SW1") (pin "B") (pinfunction "S_B") (pintype "passive"))
      (node (ref "SW1") (pin "B'") (pinfunction "S1_B'") (pintype "passive"))
      (node (ref "U1") (pin "48") (pinfunction "PWRKEY_48") (pintype "input"))
    )
    (net (code "51") (name "PWRKEY_5V") (class "Default")
      (node (ref "D5") (pin "C") (pinfunction "C_C") (pintype "passive"))
      (node (ref "JP1") (pin "6") (pinfunction "6_6") (pintype "passive"))
    )
    (net (code "52") (name "PWRSTAT") (class "Default")
      (node (ref "IC1") (pin "2") (pinfunction "I_2") (pintype "input"))
      (node (ref "U1") (pin "4") (pinfunction "STATUS_4") (pintype "output"))
    )
    (net (code "53") (name "PWRSTAT_5V") (class "Default")
      (node (ref "IC1") (pin "3") (pinfunction "O_3") (pintype "tri_state"))
      (node (ref "JP1") (pin "7") (pinfunction "7_7") (pintype "passive"))
      (node (ref "R4") (pin "2") (pinfunction "2_2") (pintype "passive"))
    )
    (net (code "54") (name "RESET") (class "Default")
      (node (ref "D6") (pin "A") (pinfunction "A_A") (pintype "passive"))
      (node (ref "U1") (pin "49") (pinfunction "RESET_49") (pintype "input"))
    )
    (net (code "55") (name "RESET_5V") (class "Default")
      (node (ref "D6") (pin "C") (pinfunction "C_C") (pintype "passive"))
      (node (ref "JP1") (pin "8") (pinfunction "8_8") (pintype "passive"))
    )
    (net (code "56") (name "RI") (class "Default")
      (node (ref "IC1") (pin "5") (pinfunction "I_5") (pintype "input"))
      (node (ref "U1") (pin "68") (pinfunction "UART_RI_68") (pintype "output"))
    )
    (net (code "57") (name "RI_5V") (class "Default")
      (node (ref "IC1") (pin "6") (pinfunction "O_6") (pintype "tri_state"))
      (node (ref "JP1") (pin "5") (pinfunction "5_5") (pintype "passive"))
    )
    (net (code "58") (name "RST") (class "Default")
      (node (ref "ATMEGA328") (pin "29") (pinfunction "PC6(/RESET)_29") (pintype "bidirectional"))
      (node (ref "C12") (pin "1") (pinfunction "1_1") (pintype "passive"))
      (node (ref "DIGITALSIDE") (pin "13") (pinfunction "13_13") (pintype "passive"))
      (node (ref "R6") (pin "2") (pinfunction "2_2") (pintype "passive"))
    )
    (net (code "59") (name "RXD_5V") (class "Default")
      (node (ref "D4") (pin "C") (pinfunction "C_C") (pintype "passive"))
      (node (ref "JP1") (pin "3") (pinfunction "3_3") (pintype "passive"))
    )
    (net (code "60") (name "SIMCLK") (class "Default")
      (node (ref "D2") (pin "4") (pinfunction "C3_4") (pintype "passive"))
      (node (ref "U1") (pin "55") (pinfunction "SIM_CLK_55") (pintype "output"))
      (node (ref "X6") (pin "C3") (pinfunction "3_C3") (pintype "passive"))
    )
    (net (code "61") (name "SIMDATA") (class "Default")
      (node (ref "D2") (pin "5") (pinfunction "C4_5") (pintype "passive"))
      (node (ref "U1") (pin "14") (pinfunction "SIM_DATA_14") (pintype "bidirectional"))
      (node (ref "X6") (pin "C7") (pinfunction "6_C7") (pintype "passive"))
    )
    (net (code "62") (name "SIMRST") (class "Default")
      (node (ref "D2") (pin "3") (pinfunction "C2_3") (pintype "passive"))
      (node (ref "U1") (pin "15") (pinfunction "SIM_RST_15") (pintype "output"))
      (node (ref "X6") (pin "C2") (pinfunction "2_C2") (pintype "passive"))
    )
    (net (code "63") (name "SPEAKER1+") (class "Default")
      (node (ref "C11") (pin "2") (pinfunction "2_2") (pintype "passive"))
      (node (ref "U1") (pin "53") (pinfunction "SPK1P_53") (pintype "output"))
    )
    (net (code "64") (name "SPEAKER2+") (class "Default")
      (node (ref "C16") (pin "1") (pinfunction "1_1") (pintype "passive"))
      (node (ref "C16") (pin "2") (pinfunction "1_2") (pintype "passive"))
      (node (ref "C17") (pin "1") (pinfunction "1_1") (pintype "passive"))
      (node (ref "C17") (pin "2") (pinfunction "1_2") (pintype "passive"))
      (node (ref "JP1") (pin "10") (pinfunction "10_10") (pintype "passive"))
      (node (ref "U1") (pin "51") (pinfunction "SPK2P/8Ω_51") (pintype "output"))
    )
    (net (code "65") (name "SPEAKER2-") (class "Default")
      (node (ref "C16") (pin "3") (pinfunction "1_3") (pintype "passive"))
      (node (ref "C16") (pin "4") (pinfunction "1_4") (pintype "passive"))
      (node (ref "C16") (pin "6") (pinfunction "2_6") (pintype "passive"))
      (node (ref "C16") (pin "7") (pinfunction "2_7") (pintype "passive"))
      (node (ref "C17") (pin "3") (pinfunction "1_3") (pintype "passive"))
      (node (ref "C17") (pin "5") (pinfunction "2_5") (pintype "passive"))
      (node (ref "C17") (pin "6") (pinfunction "2_6") (pintype "passive"))
      (node (ref "C17") (pin "7") (pinfunction "2_7") (pintype "passive"))
      (node (ref "JP1") (pin "9") (pinfunction "9_9") (pintype "passive"))
      (node (ref "U1") (pin "11") (pinfunction "SPK2N_11") (pintype "output"))
    )
    (net (code "66") (name "TXD_5V") (class "Default")
      (node (ref "IC1") (pin "8") (pinfunction "O_8") (pintype "tri_state"))
      (node (ref "JP1") (pin "4") (pinfunction "4_4") (pintype "passive"))
    )
    (net (code "67") (name "UART_RXD") (class "Default")
      (node (ref "D4") (pin "A") (pinfunction "A_A") (pintype "passive"))
      (node (ref "U1") (pin "31") (pinfunction "UART_RXD_31") (pintype "input"))
    )
    (net (code "68") (name "UART_TXD") (class "Default")
      (node (ref "IC1") (pin "9") (pinfunction "I_9") (pintype "input"))
      (node (ref "U1") (pin "32") (pinfunction "UART_TXD_32") (pintype "output"))
    )
    (net (code "69") (name "VBAT") (class "Default")
      (node (ref "C5") (pin "1") (pinfunction "1_1") (pintype "passive"))
      (node (ref "C6") (pin "1") (pinfunction "1_1") (pintype "passive"))
      (node (ref "C7") (pin "1") (pinfunction "1_1") (pintype "passive"))
      (node (ref "CN2") (pin "2") (pinfunction "2_2") (pintype "passive"))
      (node (ref "D1") (pin "C") (pinfunction "C_C") (pintype "passive"))
      (node (ref "D3") (pin "C") (pinfunction "C_C") (pintype "passive"))
      (node (ref "JP1") (pin "12") (pinfunction "12_12") (pintype "passive"))
      (node (ref "JP3") (pin "2") (pinfunction "2_2") (pintype "passive"))
      (node (ref "U1") (pin "1") (pinfunction "VBAT_1") (pintype "power_in"))
      (node (ref "U1") (pin "42") (pinfunction "VBAT_42") (pintype "power_in"))
      (node (ref "U2") (pin "3") (pinfunction "VBAT_3") (pintype "power_in"))
    )
    (net (code "70") (name "VBUS") (class "Default")
      (node (ref "U1") (pin "7") (pinfunction "VBUS_7") (pintype "power_in"))
    )
    (net (code "71") (name "VCCIO") (class "Default")
      (node (ref "IC1") (pin "14") (pinfunction "VCC_14") (pintype "power_in"))
      (node (ref "JP1") (pin "1") (pinfunction "1_1") (pintype "passive"))
    )
    (net (code "72") (name "VIO") (class "Default")
      (node (ref "+") (pin "1") (pinfunction "1_1") (pintype "passive"))
      (node (ref "ANALOGSIDE") (pin "11") (pinfunction "11_11") (pintype "passive"))
      (node (ref "ATMEGA328") (pin "18") (pinfunction "AVCC_18") (pintype "bidirectional"))
      (node (ref "ATMEGA328") (pin "4") (pinfunction "VCC_4") (pintype "bidirectional"))
      (node (ref "ATMEGA328") (pin "6") (pinfunction "VCC_6") (pintype "bidirectional"))
      (node (ref "C13") (pin "1") (pinfunction "1_1") (pintype "passive"))
      (node (ref "C19") (pin "1") (pinfunction "1_1") (pintype "passive"))
      (node (ref "IC3") (pin "2") (pinfunction "VO_2") (pintype "passive"))
      (node (ref "R6") (pin "1") (pinfunction "1_1") (pintype "passive"))
      (node (ref "RFM12B") (pin "VDD") (pinfunction "VDD_VDD") (pintype "bidirectional"))
      (node (ref "U$42") (pin "VDD") (pinfunction "VCC_VDD") (pintype "power_in"))
      (node (ref "W25X40CLSNIG-ND") (pin "3") (pinfunction "WP_3") (pintype "bidirectional"))
      (node (ref "W25X40CLSNIG-ND") (pin "7") (pinfunction "HOLD_7") (pintype "bidirectional"))
      (node (ref "W25X40CLSNIG-ND") (pin "8") (pinfunction "VCC_8") (pintype "bidirectional"))
    )
    (net (code "73") (name "VRTC") (class "Default")
      (node (ref "C9") (pin "1") (pinfunction "1_1") (pintype "passive"))
      (node (ref "U1") (pin "56") (pinfunction "VRTC_56") (pintype "power_in"))
    )
    (net (code "74") (name "unconnected-(D2-C5-Pad6)") (class "Default")
      (node (ref "D2") (pin "6") (pinfunction "C5_6") (pintype "passive"))
    )
    (net (code "75") (name "unconnected-(FTDI-Pad2)") (class "Default")
      (node (ref "FTDI") (pin "2") (pinfunction "2_2") (pintype "passive"))
    )
    (net (code "76") (name "unconnected-(U1-BPI_BUS1-Pad5)") (class "Default")
      (node (ref "U1") (pin "5") (pinfunction "BPI_BUS1_5") (pintype "output"))
    )
    (net (code "77") (name "unconnected-(U1-COL0-Pad20)") (class "Default")
      (node (ref "U1") (pin "20") (pinfunction "COL0_20") (pintype "bidirectional"))
    )
    (net (code "78") (name "unconnected-(U1-COL1-Pad25)") (class "Default")
      (node (ref "U1") (pin "25") (pinfunction "COL1_25") (pintype "bidirectional"))
    )
    (net (code "79") (name "unconnected-(U1-COL2-Pad22)") (class "Default")
      (node (ref "U1") (pin "22") (pinfunction "COL2_22") (pintype "bidirectional"))
    )
    (net (code "80") (name "unconnected-(U1-COL3-Pad21)") (class "Default")
      (node (ref "U1") (pin "21") (pinfunction "COL3_21") (pintype "bidirectional"))
    )
    (net (code "81") (name "unconnected-(U1-COL4-Pad24)") (class "Default")
      (node (ref "U1") (pin "24") (pinfunction "COL4_24") (pintype "bidirectional"))
    )
    (net (code "82") (name "unconnected-(U1-GPIO1-Pad3)") (class "Default")
      (node (ref "U1") (pin "3") (pinfunction "GPIO1_3") (pintype "bidirectional"))
    )
    (net (code "83") (name "unconnected-(U1-GPIO2-Pad27)") (class "Default")
      (node (ref "U1") (pin "27") (pinfunction "GPIO2_27") (pintype "bidirectional"))
    )
    (net (code "84") (name "unconnected-(U1-GPIO3-Pad28)") (class "Default")
      (node (ref "U1") (pin "28") (pinfunction "GPIO3_28") (pintype "bidirectional"))
    )
    (net (code "85") (name "unconnected-(U1-ISINK0-Pad47)") (class "Default")
      (node (ref "U1") (pin "47") (pinfunction "ISINK0_47") (pintype "input"))
    )
    (net (code "86") (name "unconnected-(U1-ISINK1-Pad46)") (class "Default")
      (node (ref "U1") (pin "46") (pinfunction "ISINK1_46") (pintype "input"))
    )
    (net (code "87") (name "unconnected-(U1-NC-Pad36)") (class "Default")
      (node (ref "U1") (pin "36") (pinfunction "NC_36") (pintype "no_connect"))
    )
    (net (code "88") (name "unconnected-(U1-PCMCLK-Pad29)") (class "Default")
      (node (ref "U1") (pin "29") (pinfunction "PCMCLK_29") (pintype "output"))
    )
    (net (code "89") (name "unconnected-(U1-PCMIN-Pad66)") (class "Default")
      (node (ref "U1") (pin "66") (pinfunction "PCMIN_66") (pintype "input"))
    )
    (net (code "90") (name "unconnected-(U1-PCMOUT-Pad30)") (class "Default")
      (node (ref "U1") (pin "30") (pinfunction "PCMOUT_30") (pintype "output"))
    )
    (net (code "91") (name "unconnected-(U1-PCMSYNC-Pad65)") (class "Default")
      (node (ref "U1") (pin "65") (pinfunction "PCMSYNC_65") (pintype "output"))
    )
    (net (code "92") (name "unconnected-(U1-ROW0-Pad62)") (class "Default")
      (node (ref "U1") (pin "62") (pinfunction "ROW0_62") (pintype "bidirectional"))
    )
    (net (code "93") (name "unconnected-(U1-ROW1-Pad60)") (class "Default")
      (node (ref "U1") (pin "60") (pinfunction "ROW1_60") (pintype "bidirectional"))
    )
    (net (code "94") (name "unconnected-(U1-ROW2-Pad61)") (class "Default")
      (node (ref "U1") (pin "61") (pinfunction "ROW2_61") (pintype "bidirectional"))
    )
    (net (code "95") (name "unconnected-(U1-ROW3-Pad23)") (class "Default")
      (node (ref "U1") (pin "23") (pinfunction "ROW3_23") (pintype "bidirectional"))
    )
    (net (code "96") (name "unconnected-(U1-ROW4-Pad63)") (class "Default")
      (node (ref "U1") (pin "63") (pinfunction "ROW4_63") (pintype "bidirectional"))
    )
    (net (code "97") (name "unconnected-(U1-SCL-Pad74)") (class "Default")
      (node (ref "U1") (pin "74") (pinfunction "SCL_74") (pintype "bidirectional"))
    )
    (net (code "98") (name "unconnected-(U1-SDA-Pad75)") (class "Default")
      (node (ref "U1") (pin "75") (pinfunction "SDA_75") (pintype "bidirectional"))
    )
    (net (code "99") (name "unconnected-(U1-SIMPRE-Pad54)") (class "Default")
      (node (ref "U1") (pin "54") (pinfunction "SIMPRE_54") (pintype "input"))
    )
    (net (code "100") (name "unconnected-(U1-SPK1N-Pad13)") (class "Default")
      (node (ref "U1") (pin "13") (pinfunction "SPK1N_13") (pintype "output"))
    )
    (net (code "101") (name "unconnected-(U1-UART_CTS-Pad34)") (class "Default")
      (node (ref "U1") (pin "34") (pinfunction "UART_CTS_34") (pintype "output"))
    )
    (net (code "102") (name "unconnected-(U1-UART_DCD-Pad70)") (class "Default")
      (node (ref "U1") (pin "70") (pinfunction "UART_DCD_70") (pintype "input"))
    )
    (net (code "103") (name "unconnected-(U1-UART_DTR-Pad69)") (class "Default")
      (node (ref "U1") (pin "69") (pinfunction "UART_DTR_69") (pintype "input"))
    )
    (net (code "104") (name "unconnected-(U1-UART_RTS-Pad33)") (class "Default")
      (node (ref "U1") (pin "33") (pinfunction "UART_RTS_33") (pintype "input"))
    )
    (net (code "105") (name "unconnected-(U1-USB_DM-Pad19)") (class "Default")
      (node (ref "U1") (pin "19") (pinfunction "USB_DM_19") (pintype "bidirectional"))
    )
    (net (code "106") (name "unconnected-(U1-USB_DP-Pad59)") (class "Default")
      (node (ref "U1") (pin "59") (pinfunction "USB_DP_59") (pintype "bidirectional"))
    )
    (net (code "107") (name "unconnected-(X2-PadD+)") (class "Default")
      (node (ref "X2") (pin "D+") (pinfunction "D+_D+") (pintype "bidirectional"))
    )
    (net (code "108") (name "unconnected-(X2-PadD-)") (class "Default")
      (node (ref "X2") (pin "D-") (pinfunction "D-_D-") (pintype "bidirectional"))
    )
    (net (code "109") (name "unconnected-(X2-PadID)") (class "Default")
      (node (ref "X2") (pin "ID") (pinfunction "ID_ID") (pintype "bidirectional"))
    )
    (net (code "110") (name "unconnected-(X6-5-PadC6)") (class "Default")
      (node (ref "X6") (pin "C6") (pinfunction "5_C6") (pintype "passive"))
    )
  )
)
